# 51.net
KiCad netlist of a schematic drawn in Altium Designer
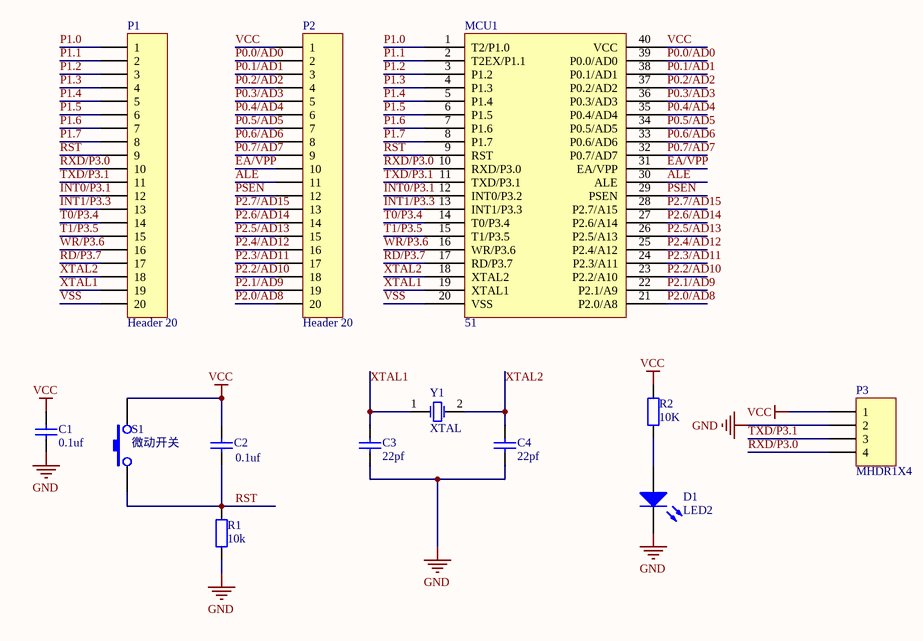
[diagram p0: 51.SchDoc]

(export (version "E")
  (design (tool "Eeschema 10.0.6"))
  (components
    (comp (ref "C1")
      (value "0.1uf")
      (footprint "RB.15/.3")
      (description "电容")
      (libsource (lib "mylib") (part "C"))
    )
    (comp (ref "C2")
      (value "0.1uf")
      (footprint "0603")
      (description "电容")
      (libsource (lib "mylib") (part "C"))
    )
    (comp (ref "C3")
      (value "22pf")
      (footprint "RB.15/.3")
      (description "电容")
      (libsource (lib "mylib") (part "C"))
    )
    (comp (ref "C4")
      (value "22pf")
      (footprint "RB.15/.3")
      (description "电容")
      (libsource (lib "mylib") (part "C"))
    )
    (comp (ref "D1")
      (value "LED2")
      (footprint "3.2X1.6X1.1")
      (description "Typical RED, GREEN, YELLOW, AMBER GaAs LED")
      (fields (field (name "PUBLISHER") "Altium Limited"))
      (libsource (lib "Miscellaneous Devices") (part "LED2"))
    )
    (comp (ref "MCU1") (value "51") (footprint "51-DIP40") (libsource (lib "51") (part "51-DIP")))
    (comp (ref "P1")
      (value "Header 20")
      (footprint "HDR1X20")
      (description "Header, 20-Pin")
      (fields (field (name "PUBLISHER") "Altium Limited"))
      (libsource (lib "Miscellaneous Connectors") (part "Header 20"))
    )
    (comp (ref "P2")
      (value "Header 20")
      (footprint "HDR1X20")
      (description "Header, 20-Pin")
      (fields (field (name "PUBLISHER") "Altium Limited"))
      (libsource (lib "Miscellaneous Connectors") (part "Header 20"))
    )
    (comp (ref "P3")
      (value "MHDR1X4")
      (footprint "MHDR1X4")
      (description "Header, 4-Pin")
      (fields (field (name "PUBLISHER") "Altium Limited"))
      (libsource (lib "Miscellaneous Connectors") (part "MHDR1X4"))
    )
    (comp (ref "R1")
      (value "10k")
      (footprint "AXIAL0.4")
      (description "电阻")
      (libsource (lib "mylib") (part "R"))
    )
    (comp (ref "R2") (value "10K") (footprint "0603") (description "电阻") (libsource (lib "mylib") (part "R")))
    (comp (ref "S1") (value "微动开关") (footprint "KEY") (libsource (lib "mylib") (part "微动开关")))
    (comp (ref "Y1")
      (value "XTAL")
      (footprint "XTAL1")
      (description "晶振")
      (libsource (lib "mylib") (part "XTAL"))
    )
  )
  (nets
    (net (code "1") (name "/ALE") (class "Default")
      (node (ref "MCU1") (pin "30") (pinfunction "ALE_30") (pintype "passive"))
      (node (ref "P2") (pin "11") (pinfunction "11_11") (pintype "passive"))
    )
    (net (code "2") (name "/EA{slash}VPP") (class "Default")
      (node (ref "MCU1") (pin "31") (pinfunction "EA/VPP_31") (pintype "passive"))
      (node (ref "P2") (pin "10") (pinfunction "10_10") (pintype "passive"))
    )
    (net (code "3") (name "/INT0{slash}P3.1") (class "Default")
      (node (ref "MCU1") (pin "12") (pinfunction "INT0/P3.2_12") (pintype "passive"))
      (node (ref "P1") (pin "12") (pinfunction "12_12") (pintype "passive"))
    )
    (net (code "4") (name "/INT1{slash}P3.3") (class "Default")
      (node (ref "MCU1") (pin "13") (pinfunction "INT1/P3.3_13") (pintype "passive"))
      (node (ref "P1") (pin "13") (pinfunction "13_13") (pintype "passive"))
    )
    (net (code "5") (name "/P0.0{slash}AD0") (class "Default")
      (node (ref "MCU1") (pin "39") (pinfunction "P0.0/AD0_39") (pintype "passive"))
      (node (ref "P2") (pin "2") (pinfunction "2_2") (pintype "passive"))
    )
    (net (code "6") (name "/P0.1{slash}AD1") (class "Default")
      (node (ref "MCU1") (pin "38") (pinfunction "P0.1/AD1_38") (pintype "passive"))
      (node (ref "P2") (pin "3") (pinfunction "3_3") (pintype "passive"))
    )
    (net (code "7") (name "/P0.2{slash}AD2") (class "Default")
      (node (ref "MCU1") (pin "37") (pinfunction "P0.2/AD2_37") (pintype "passive"))
      (node (ref "P2") (pin "4") (pinfunction "4_4") (pintype "passive"))
    )
    (net (code "8") (name "/P0.3{slash}AD3") (class "Default")
      (node (ref "MCU1") (pin "36") (pinfunction "P0.3/AD3_36") (pintype "passive"))
      (node (ref "P2") (pin "5") (pinfunction "5_5") (pintype "passive"))
    )
    (net (code "9") (name "/P0.4{slash}AD4") (class "Default")
      (node (ref "MCU1") (pin "35") (pinfunction "P0.4/AD4_35") (pintype "passive"))
      (node (ref "P2") (pin "6") (pinfunction "6_6") (pintype "passive"))
    )
    (net (code "10") (name "/P0.5{slash}AD5") (class "Default")
      (node (ref "MCU1") (pin "34") (pinfunction "P0.5/AD5_34") (pintype "passive"))
      (node (ref "P2") (pin "7") (pinfunction "7_7") (pintype "passive"))
    )
    (net (code "11") (name "/P0.6{slash}AD6") (class "Default")
      (node (ref "MCU1") (pin "33") (pinfunction "P0.6/AD6_33") (pintype "passive"))
      (node (ref "P2") (pin "8") (pinfunction "8_8") (pintype "passive"))
    )
    (net (code "12") (name "/P0.7{slash}AD7") (class "Default")
      (node (ref "MCU1") (pin "32") (pinfunction "P0.7/AD7_32") (pintype "passive"))
      (node (ref "P2") (pin "9") (pinfunction "9_9") (pintype "passive"))
    )
    (net (code "13") (name "/P1.0") (class "Default")
      (node (ref "MCU1") (pin "1") (pinfunction "T2/P1.0_1") (pintype "passive"))
      (node (ref "P1") (pin "1") (pinfunction "1_1") (pintype "passive"))
    )
    (net (code "14") (name "/P1.1") (class "Default")
      (node (ref "MCU1") (pin "2") (pinfunction "T2EX/P1.1_2") (pintype "passive"))
      (node (ref "P1") (pin "2") (pinfunction "2_2") (pintype "passive"))
    )
    (net (code "15") (name "/P1.2") (class "Default")
      (node (ref "MCU1") (pin "3") (pinfunction "P1.2_3") (pintype "passive"))
      (node (ref "P1") (pin "3") (pinfunction "3_3") (pintype "passive"))
    )
    (net (code "16") (name "/P1.3") (class "Default")
      (node (ref "MCU1") (pin "4") (pinfunction "P1.3_4") (pintype "passive"))
      (node (ref "P1") (pin "4") (pinfunction "4_4") (pintype "passive"))
    )
    (net (code "17") (name "/P1.4") (class "Default")
      (node (ref "MCU1") (pin "5") (pinfunction "P1.4_5") (pintype "passive"))
      (node (ref "P1") (pin "5") (pinfunction "5_5") (pintype "passive"))
    )
    (net (code "18") (name "/P1.5") (class "Default")
      (node (ref "MCU1") (pin "6") (pinfunction "P1.5_6") (pintype "passive"))
      (node (ref "P1") (pin "6") (pinfunction "6_6") (pintype "passive"))
    )
    (net (code "19") (name "/P1.6") (class "Default")
      (node (ref "MCU1") (pin "7") (pinfunction "P1.6_7") (pintype "passive"))
      (node (ref "P1") (pin "7") (pinfunction "7_7") (pintype "passive"))
    )
    (net (code "20") (name "/P1.7") (class "Default")
      (node (ref "MCU1") (pin "8") (pinfunction "P1.7_8") (pintype "passive"))
      (node (ref "P1") (pin "8") (pinfunction "8_8") (pintype "passive"))
    )
    (net (code "21") (name "/P2.0{slash}AD8") (class "Default")
      (node (ref "MCU1") (pin "21") (pinfunction "P2.0/A8_21") (pintype "passive"))
      (node (ref "P2") (pin "20") (pinfunction "20_20") (pintype "passive"))
    )
    (net (code "22") (name "/P2.1{slash}AD9") (class "Default")
      (node (ref "MCU1") (pin "22") (pinfunction "P2.1/A9_22") (pintype "passive"))
      (node (ref "P2") (pin "19") (pinfunction "19_19") (pintype "passive"))
    )
    (net (code "23") (name "/P2.2{slash}AD10") (class "Default")
      (node (ref "MCU1") (pin "23") (pinfunction "P2.2/A10_23") (pintype "passive"))
      (node (ref "P2") (pin "18") (pinfunction "18_18") (pintype "passive"))
    )
    (net (code "24") (name "/P2.3{slash}AD11") (class "Default")
      (node (ref "MCU1") (pin "24") (pinfunction "P2.3/A11_24") (pintype "passive"))
      (node (ref "P2") (pin "17") (pinfunction "17_17") (pintype "passive"))
    )
    (net (code "25") (name "/P2.4{slash}AD12") (class "Default")
      (node (ref "MCU1") (pin "25") (pinfunction "P2.4/A12_25") (pintype "passive"))
      (node (ref "P2") (pin "16") (pinfunction "16_16") (pintype "passive"))
    )
    (net (code "26") (name "/P2.5{slash}AD13") (class "Default")
      (node (ref "MCU1") (pin "26") (pinfunction "P2.5/A13_26") (pintype "passive"))
      (node (ref "P2") (pin "15") (pinfunction "15_15") (pintype "passive"))
    )
    (net (code "27") (name "/P2.6{slash}AD14") (class "Default")
      (node (ref "MCU1") (pin "27") (pinfunction "P2.6/A14_27") (pintype "passive"))
      (node (ref "P2") (pin "14") (pinfunction "14_14") (pintype "passive"))
    )
    (net (code "28") (name "/P2.7{slash}AD15") (class "Default")
      (node (ref "MCU1") (pin "28") (pinfunction "P2.7/A15_28") (pintype "passive"))
      (node (ref "P2") (pin "13") (pinfunction "13_13") (pintype "passive"))
    )
    (net (code "29") (name "/PSEN") (class "Default")
      (node (ref "MCU1") (pin "29") (pinfunction "PSEN_29") (pintype "passive"))
      (node (ref "P2") (pin "12") (pinfunction "12_12") (pintype "passive"))
    )
    (net (code "30") (name "/RD{slash}P3.7") (class "Default")
      (node (ref "MCU1") (pin "17") (pinfunction "RD/P3.7_17") (pintype "passive"))
      (node (ref "P1") (pin "17") (pinfunction "17_17") (pintype "passive"))
    )
    (net (code "31") (name "/RST") (class "Default")
      (node (ref "C2") (pin "1") (pinfunction "1_1") (pintype "passive"))
      (node (ref "MCU1") (pin "9") (pinfunction "RST_9") (pintype "passive"))
      (node (ref "P1") (pin "9") (pinfunction "9_9") (pintype "passive"))
      (node (ref "R1") (pin "2") (pinfunction "2_2") (pintype "passive"))
      (node (ref "S1") (pin "1") (pinfunction "1_1") (pintype "passive"))
    )
    (net (code "32") (name "/RXD{slash}P3.0") (class "Default")
      (node (ref "MCU1") (pin "10") (pinfunction "RXD/P3.0_10") (pintype "passive"))
      (node (ref "P1") (pin "10") (pinfunction "10_10") (pintype "passive"))
      (node (ref "P3") (pin "4") (pinfunction "4_4") (pintype "passive"))
    )
    (net (code "33") (name "/T0{slash}P3.4") (class "Default")
      (node (ref "MCU1") (pin "14") (pinfunction "T0/P3.4_14") (pintype "passive"))
      (node (ref "P1") (pin "14") (pinfunction "14_14") (pintype "passive"))
    )
    (net (code "34") (name "/T1{slash}P3.5") (class "Default")
      (node (ref "MCU1") (pin "15") (pinfunction "T1/P3.5_15") (pintype "passive"))
      (node (ref "P1") (pin "15") (pinfunction "15_15") (pintype "passive"))
    )
    (net (code "35") (name "/TXD{slash}P3.1") (class "Default")
      (node (ref "MCU1") (pin "11") (pinfunction "TXD/P3.1_11") (pintype "passive"))
      (node (ref "P1") (pin "11") (pinfunction "11_11") (pintype "passive"))
      (node (ref "P3") (pin "3") (pinfunction "3_3") (pintype "passive"))
    )
    (net (code "36") (name "/VSS") (class "Default")
      (node (ref "MCU1") (pin "20") (pinfunction "VSS_20") (pintype "passive"))
      (node (ref "P1") (pin "20") (pinfunction "20_20") (pintype "passive"))
    )
    (net (code "37") (name "/WR{slash}P3.6") (class "Default")
      (node (ref "MCU1") (pin "16") (pinfunction "WR/P3.6_16") (pintype "passive"))
      (node (ref "P1") (pin "16") (pinfunction "16_16") (pintype "passive"))
    )
    (net (code "38") (name "/XTAL1") (class "Default")
      (node (ref "C3") (pin "2") (pinfunction "2_2") (pintype "passive"))
      (node (ref "MCU1") (pin "19") (pinfunction "XTAL1_19") (pintype "passive"))
      (node (ref "P1") (pin "19") (pinfunction "19_19") (pintype "passive"))
      (node (ref "Y1") (pin "1") (pinfunction "1_1") (pintype "passive"))
    )
    (net (code "39") (name "/XTAL2") (class "Default")
      (node (ref "C4") (pin "2") (pinfunction "2_2") (pintype "passive"))
      (node (ref "MCU1") (pin "18") (pinfunction "XTAL2_18") (pintype "passive"))
      (node (ref "P1") (pin "18") (pinfunction "18_18") (pintype "passive"))
      (node (ref "Y1") (pin "2") (pinfunction "2_2") (pintype "passive"))
    )
    (net (code "40") (name "GND") (class "Default")
      (node (ref "C1") (pin "1") (pinfunction "1_1") (pintype "passive"))
      (node (ref "C3") (pin "1") (pinfunction "1_1") (pintype "passive"))
      (node (ref "C4") (pin "1") (pinfunction "1_1") (pintype "passive"))
      (node (ref "D1") (pin "2") (pinfunction "K_2") (pintype "passive"))
      (node (ref "P3") (pin "2") (pinfunction "2_2") (pintype "passive"))
      (node (ref "R1") (pin "1") (pinfunction "1_1") (pintype "passive"))
    )
    (net (code "41") (name "Net-(D1-A)") (class "Default")
      (node (ref "D1") (pin "1") (pinfunction "A_1") (pintype "passive"))
      (node (ref "R2") (pin "1") (pinfunction "1_1") (pintype "passive"))
    )
    (net (code "42") (name "VCC") (class "Default")
      (node (ref "C1") (pin "2") (pinfunction "2_2") (pintype "passive"))
      (node (ref "C2") (pin "2") (pinfunction "2_2") (pintype "passive"))
      (node (ref "MCU1") (pin "40") (pinfunction "VCC_40") (pintype "passive"))
      (node (ref "P2") (pin "1") (pinfunction "1_1") (pintype "passive"))
      (node (ref "P3") (pin "1") (pinfunction "1_1") (pintype "passive"))
      (node (ref "R2") (pin "2") (pinfunction "2_2") (pintype "passive"))
      (node (ref "S1") (pin "2") (pinfunction "2_2") (pintype "passive"))
    )
  )
)
